# n2k-breakout-7_0-ISO.net
KiCad netlist of a schematic drawn in EAGLE
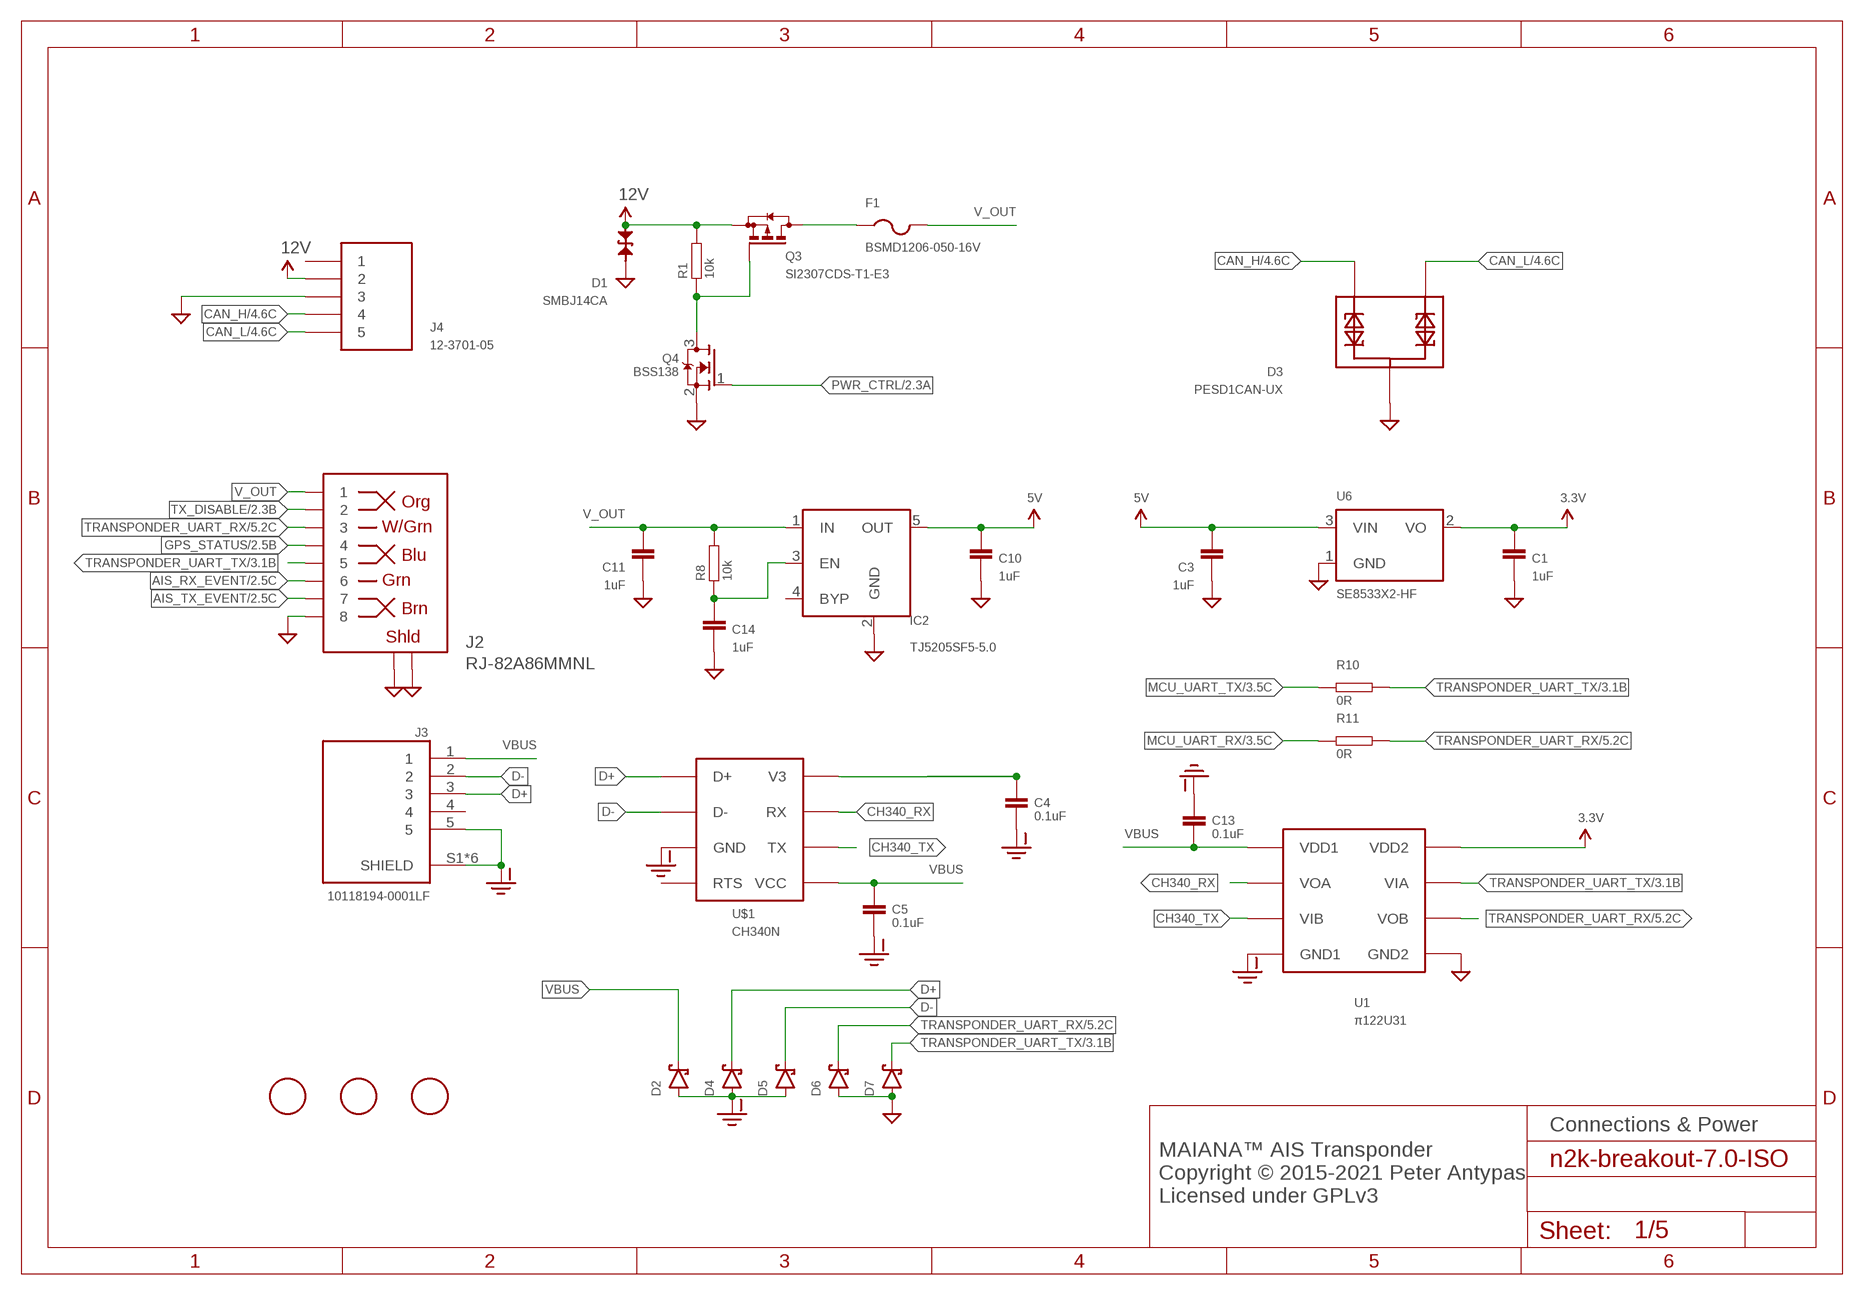
[diagram p0: schematic, sheet 1]
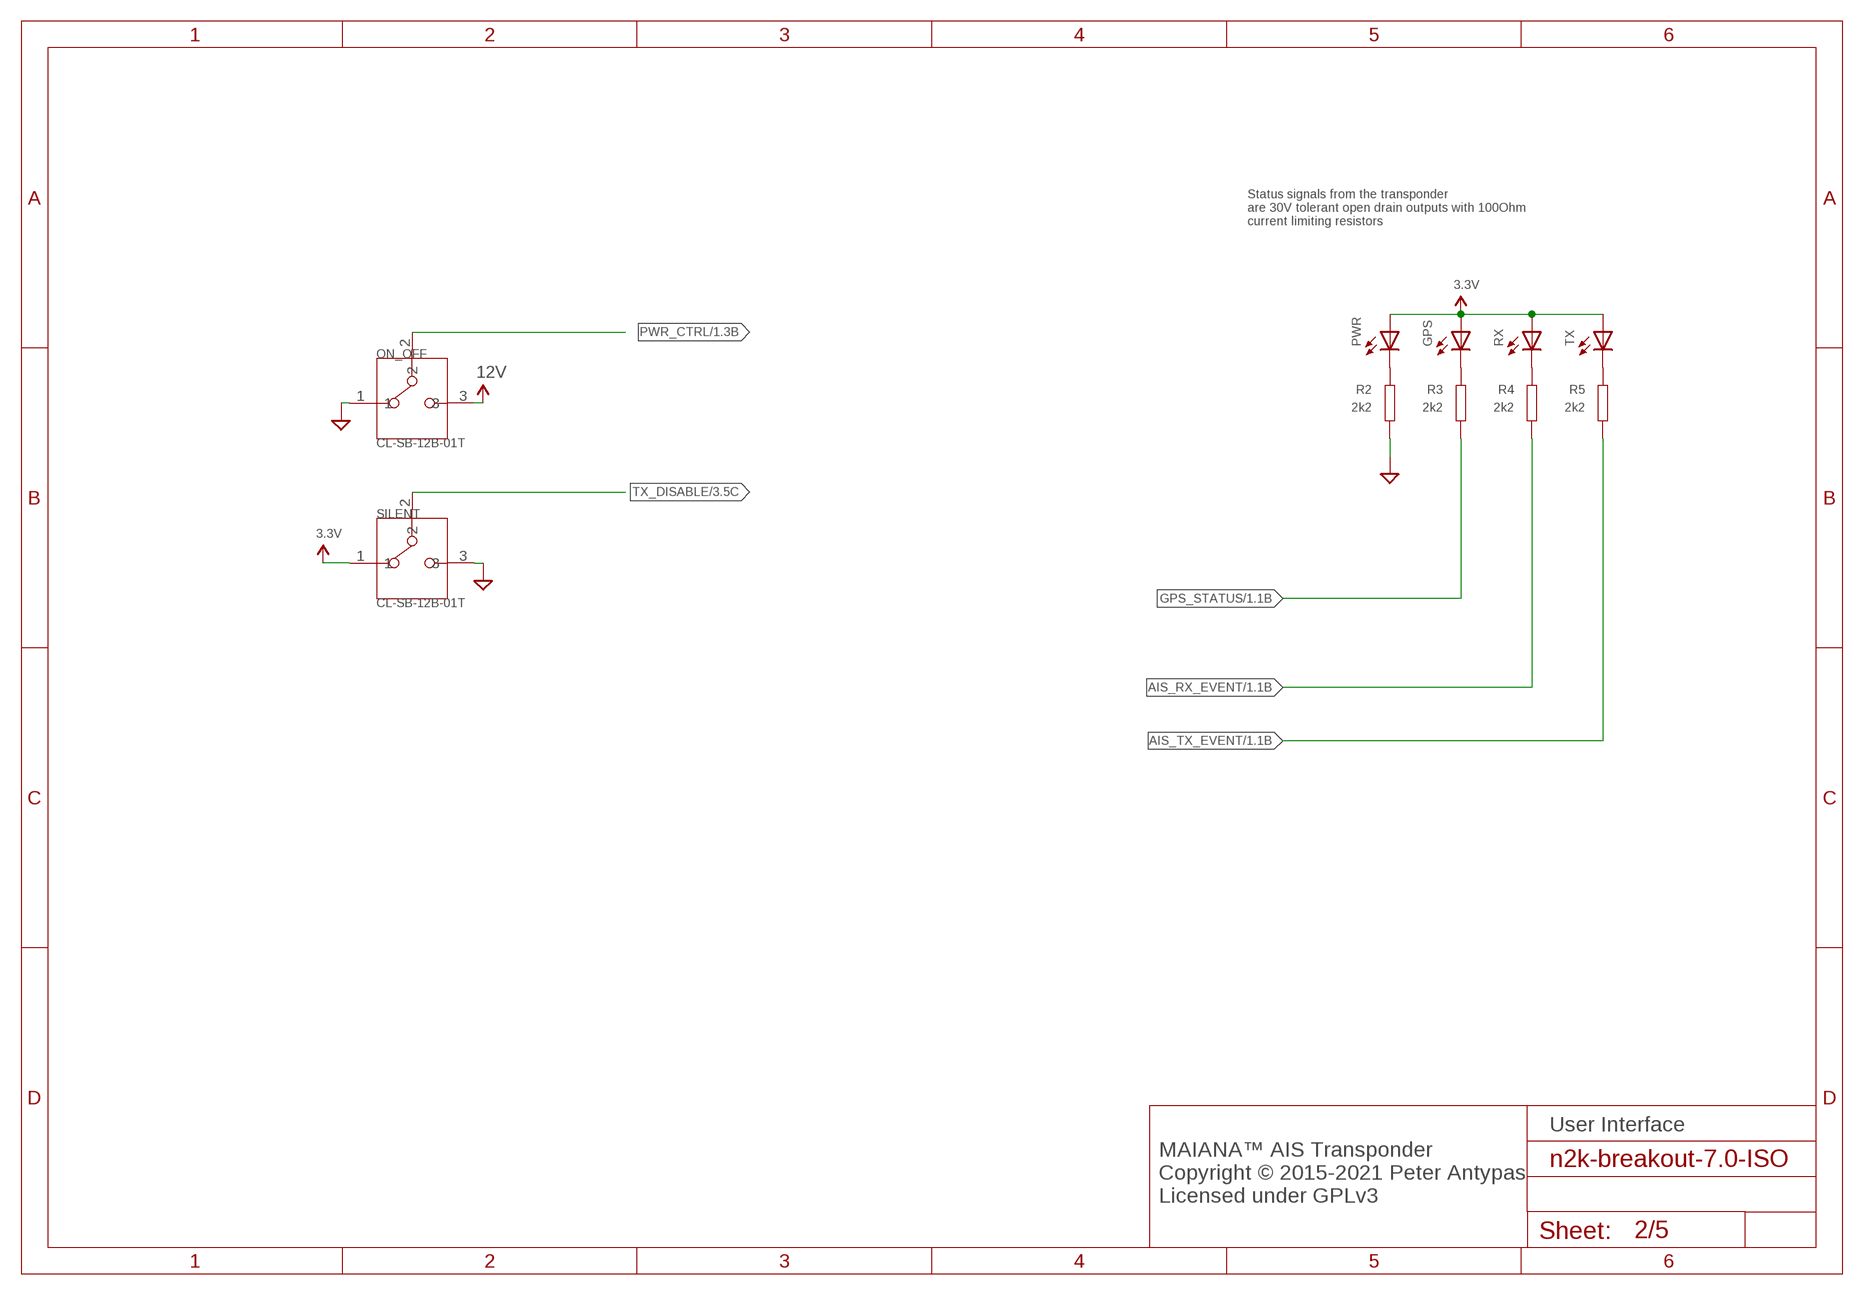
[diagram p1: schematic, sheet 2]
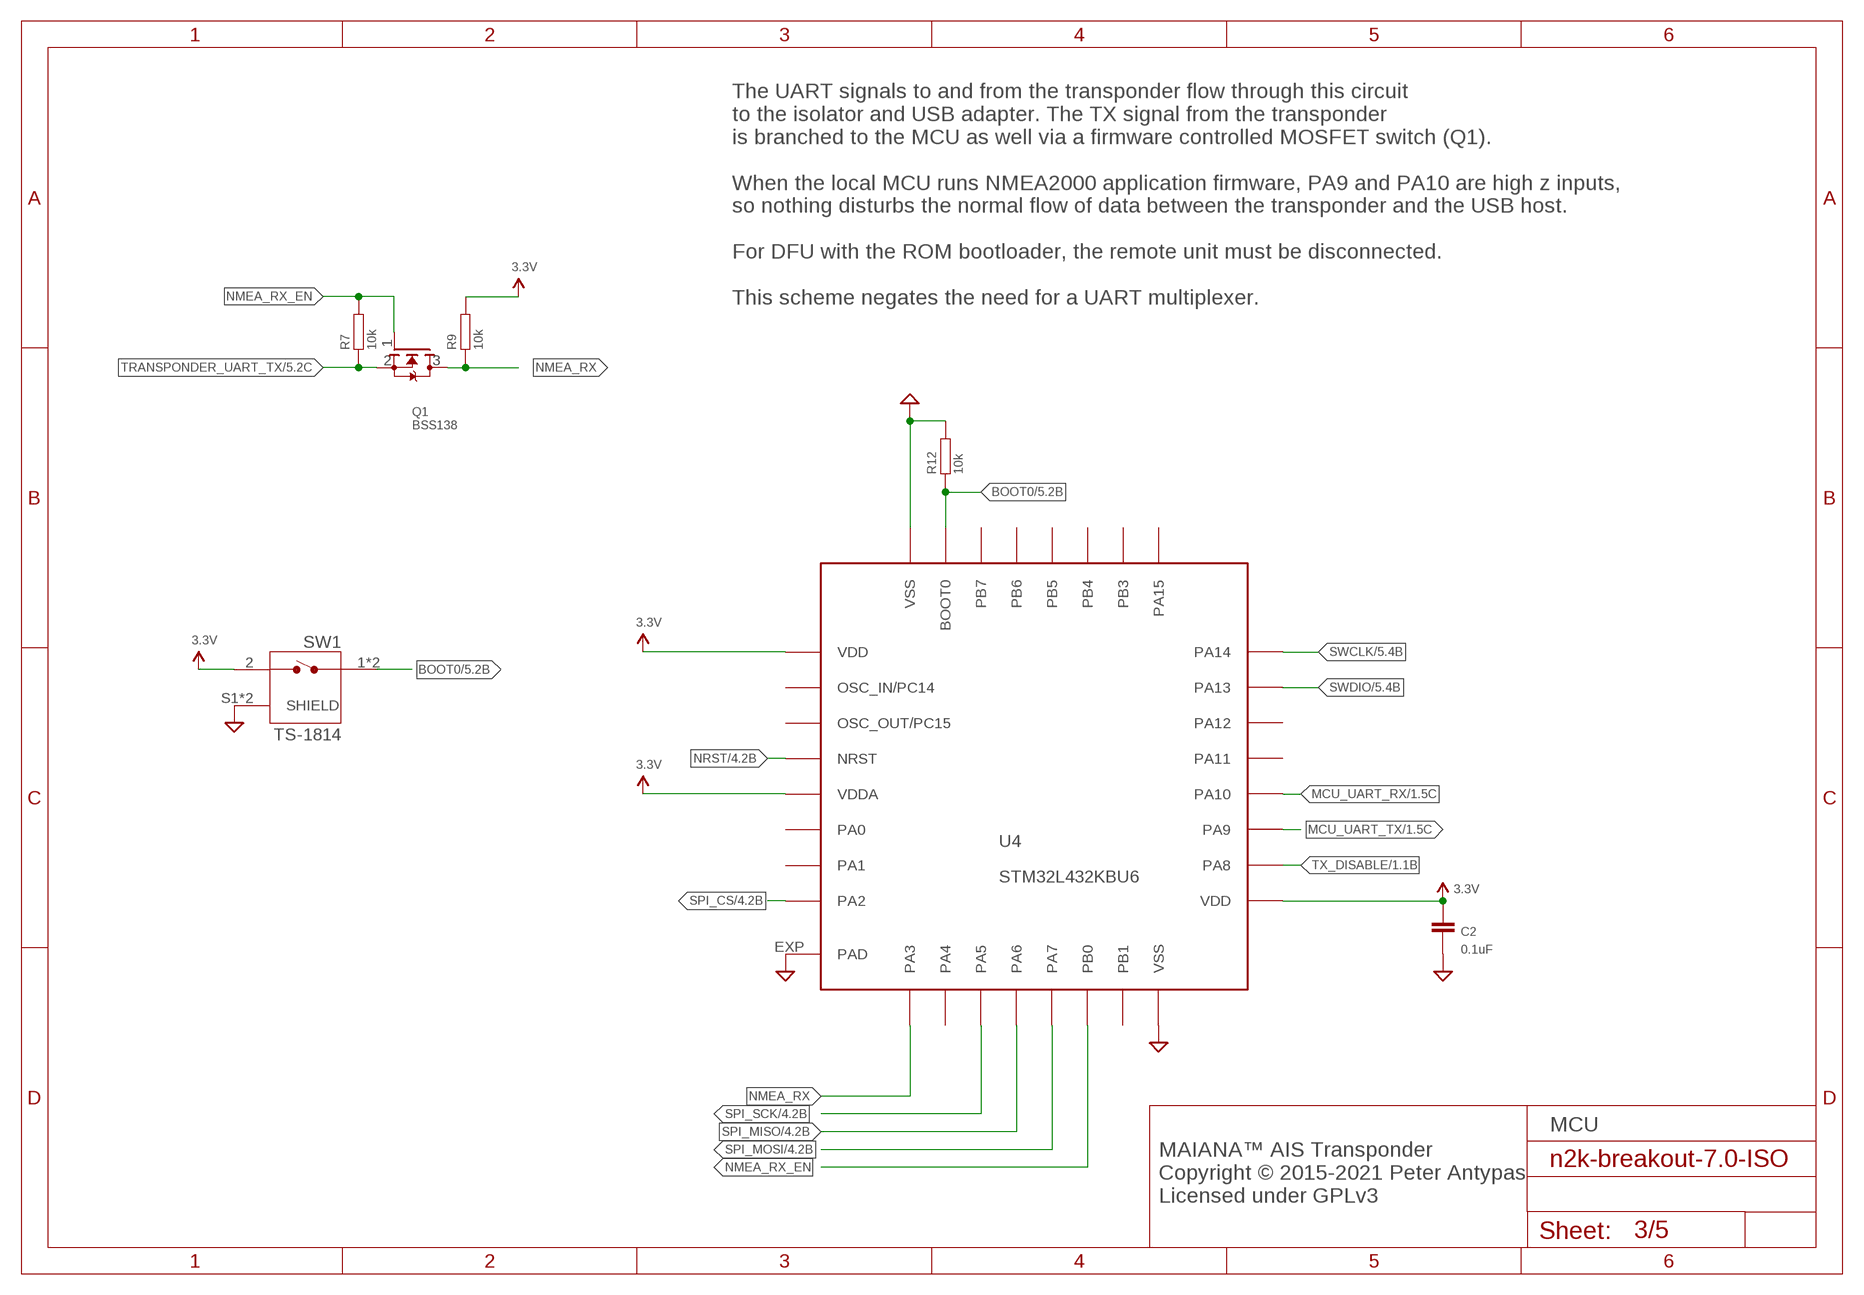
[diagram p2: schematic, sheet 3]
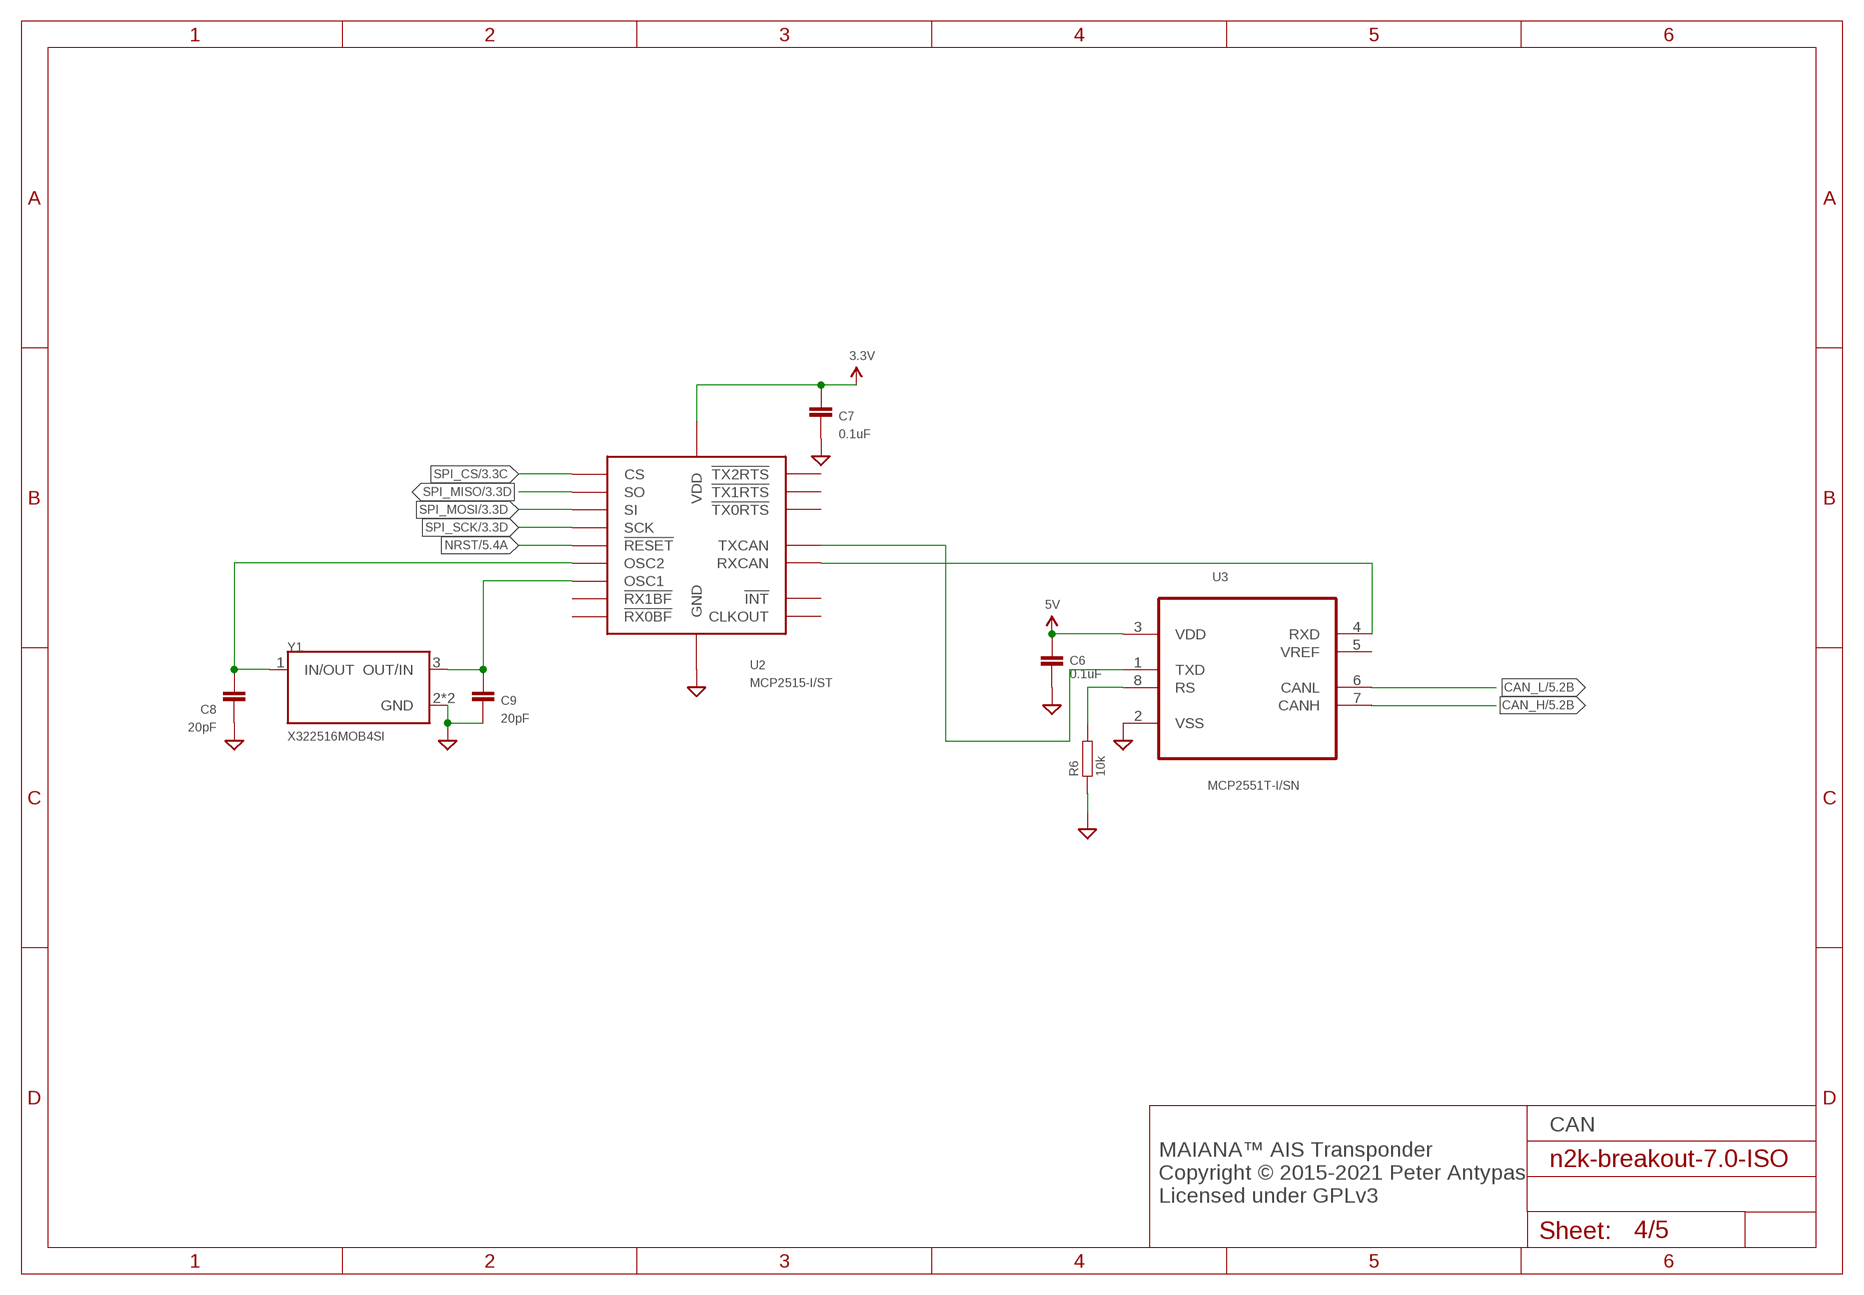
[diagram p3: schematic, sheet 4]
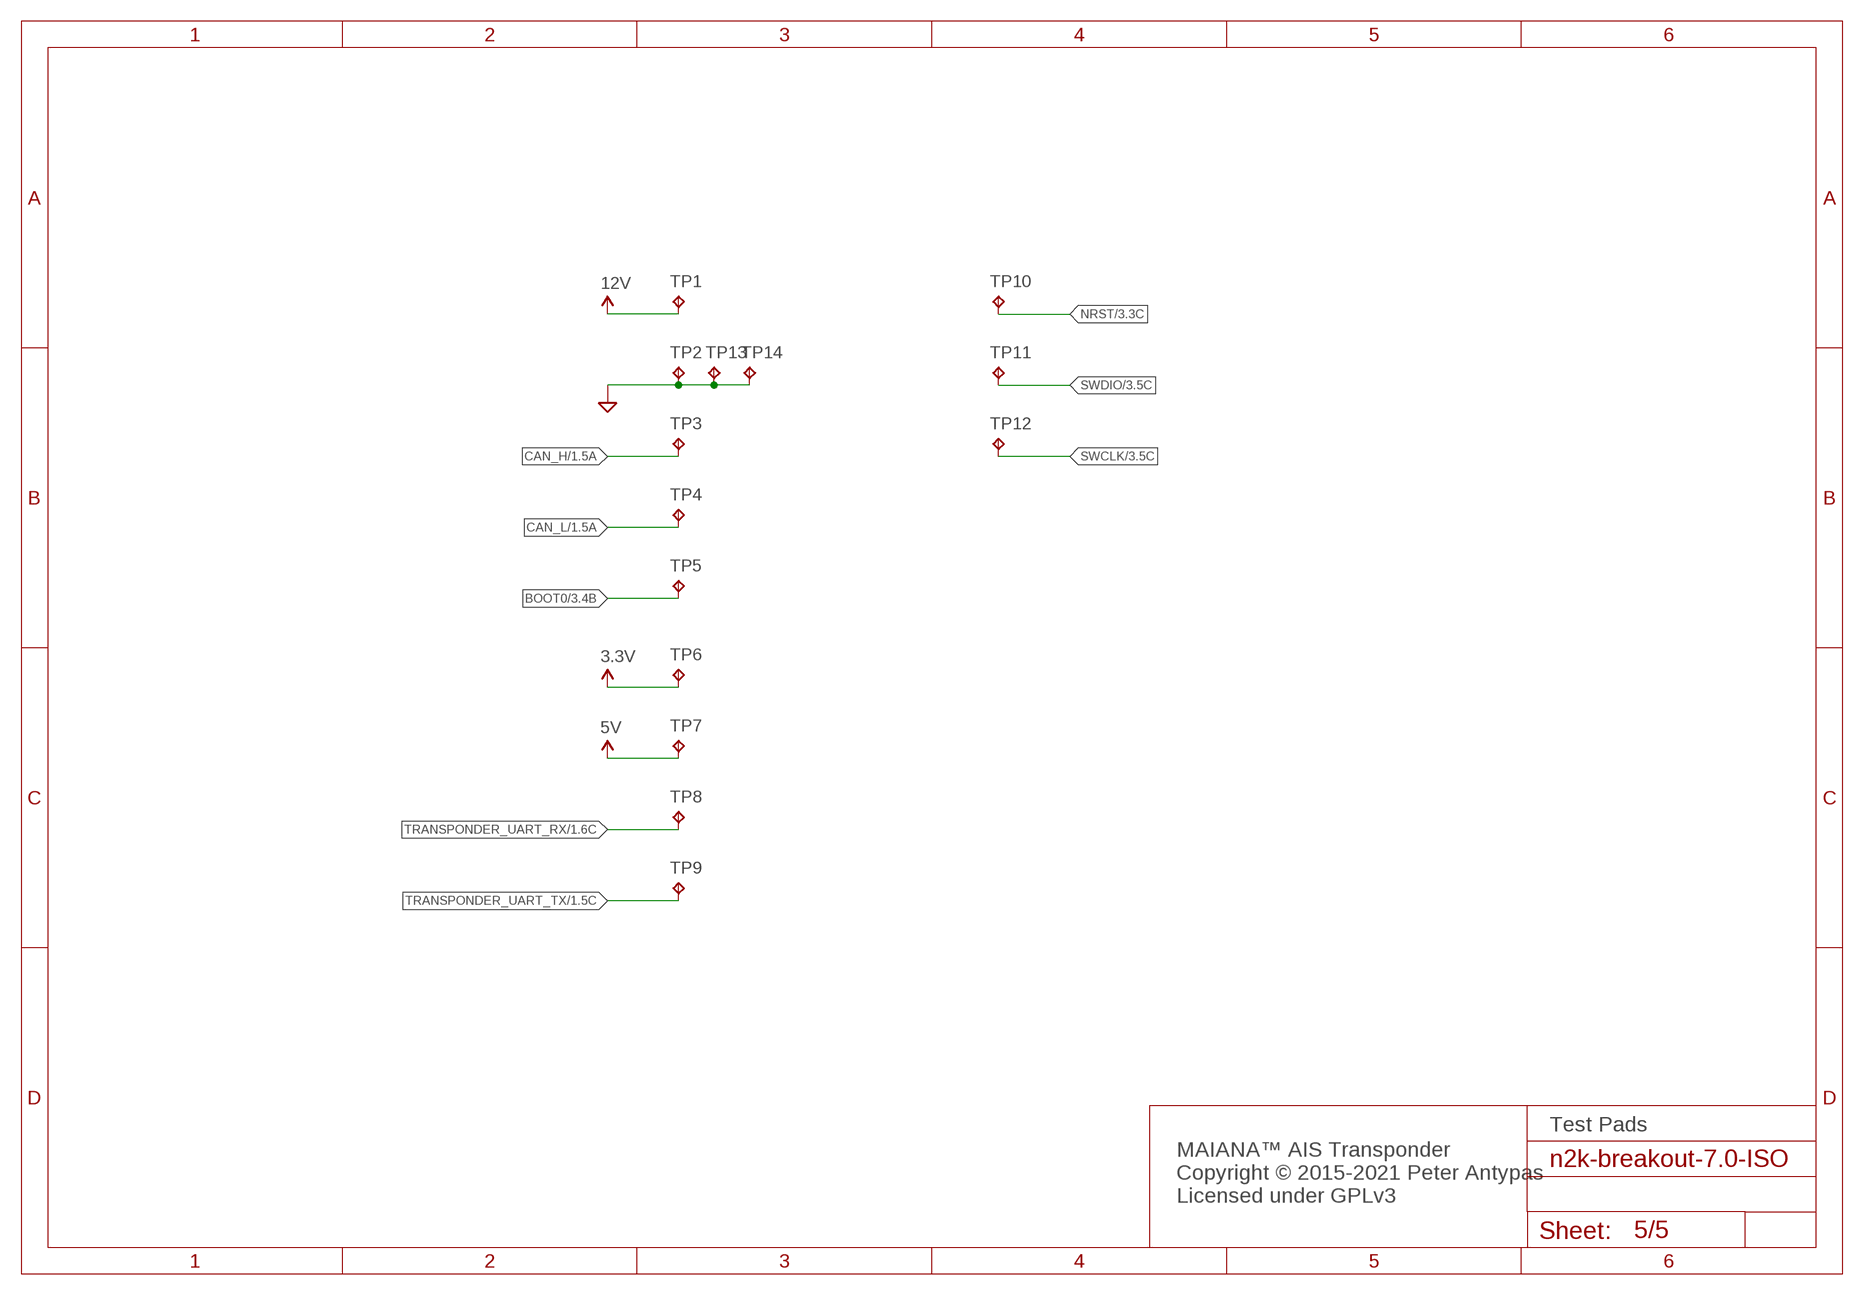
[diagram p4: schematic, sheet 5]

(export (version "E")
  (design (tool "Eeschema 10.0.6"))
  (components
    (comp (ref "TP1")
      (value "TPTP12R")
      (footprint "eagle-import:TP12R")
      (libsource (lib "eagle-import") (part "TPTP12R"))
    )
    (comp (ref "TP2")
      (value "TPTP12R")
      (footprint "eagle-import:TP12R")
      (libsource (lib "eagle-import") (part "TPTP12R"))
    )
    (comp (ref "TP3")
      (value "TPTP12R")
      (footprint "eagle-import:TP12R")
      (libsource (lib "eagle-import") (part "TPTP12R"))
    )
    (comp (ref "TP4")
      (value "TPTP12R")
      (footprint "eagle-import:TP12R")
      (libsource (lib "eagle-import") (part "TPTP12R"))
    )
    (comp (ref "TP5")
      (value "TPTP12R")
      (footprint "eagle-import:TP12R")
      (libsource (lib "eagle-import") (part "TPTP12R"))
    )
    (comp (ref "TP6")
      (value "TPTP12R")
      (footprint "eagle-import:TP12R")
      (libsource (lib "eagle-import") (part "TPTP12R"))
    )
    (comp (ref "TP7")
      (value "TPTP12R")
      (footprint "eagle-import:TP12R")
      (libsource (lib "eagle-import") (part "TPTP12R"))
    )
    (comp (ref "TP8")
      (value "TPTP12R")
      (footprint "eagle-import:TP12R")
      (libsource (lib "eagle-import") (part "TPTP12R"))
    )
    (comp (ref "TP9")
      (value "TPTP12R")
      (footprint "eagle-import:TP12R")
      (libsource (lib "eagle-import") (part "TPTP12R"))
    )
    (comp (ref "TP10")
      (value "TPTP12R")
      (footprint "eagle-import:TP12R")
      (libsource (lib "eagle-import") (part "TPTP12R"))
    )
    (comp (ref "TP11")
      (value "TPTP12R")
      (footprint "eagle-import:TP12R")
      (libsource (lib "eagle-import") (part "TPTP12R"))
    )
    (comp (ref "TP12")
      (value "TPTP12R")
      (footprint "eagle-import:TP12R")
      (libsource (lib "eagle-import") (part "TPTP12R"))
    )
    (comp (ref "TP13")
      (value "TPTP12R")
      (footprint "eagle-import:TP12R")
      (libsource (lib "eagle-import") (part "TPTP12R"))
    )
    (comp (ref "TP14")
      (value "TPTP12R")
      (footprint "eagle-import:TP12R")
      (libsource (lib "eagle-import") (part "TPTP12R"))
    )
    (comp (ref "C6")
      (value "0.1uF")
      (footprint "eagle-import:0603")
      (fields (field (name "PARTNO") "06035C104KAT2A "))
      (libsource (lib "eagle-import") (part "CAPACITOR0603"))
    )
    (comp (ref "C7")
      (value "0.1uF")
      (footprint "eagle-import:0603")
      (fields (field (name "PARTNO") "06035C104KAT2A "))
      (libsource (lib "eagle-import") (part "CAPACITOR0603"))
    )
    (comp (ref "C8")
      (value "20pF")
      (footprint "eagle-import:0603")
      (fields (field (name "PARTNO") "GRM1885C1H200JA01D "))
      (libsource (lib "eagle-import") (part "CAPACITOR0603"))
    )
    (comp (ref "C9")
      (value "20pF")
      (footprint "eagle-import:0603")
      (fields (field (name "PARTNO") "GRM1885C1H200JA01D "))
      (libsource (lib "eagle-import") (part "CAPACITOR0603"))
    )
    (comp (ref "R6")
      (value "10k")
      (footprint "eagle-import:0603")
      (fields (field (name "PARTNO") "RC0603FR-0710KL"))
      (libsource (lib "eagle-import") (part "RESISTOR0603"))
    )
    (comp (ref "U2")
      (value "MCP2515-I/ST")
      (footprint "eagle-import:TSSOP20")
      (libsource (lib "eagle-import") (part "MCP2515TSSOP20"))
    )
    (comp (ref "U3")
      (value "MCP2551T-I/SN")
      (footprint "eagle-import:SOIC127P600X175-8N")
      (fields (field (name "MF") "Microchip"))
      (libsource (lib "eagle-import") (part "MCP2551T-I/SN"))
    )
    (comp (ref "Y1")
      (value "X322516MOB4SI")
      (footprint "eagle-import:XTAL_ECS-160-10-36-JGN-TR")
      (fields (field (name "MF") "ECS Inc.") (field (name "MP") "ECS-300-8-36CKM-TR"))
      (libsource (lib "eagle-import") (part "ECS-300-8-36CKM-TR"))
    )
    (comp (ref "C1")
      (value "1uF")
      (footprint "eagle-import:0603")
      (fields (field (name "PARTNO") "CC0603KRX5R8BB105"))
      (libsource (lib "eagle-import") (part "CAPACITOR0603"))
    )
    (comp (ref "C3")
      (value "1uF")
      (footprint "eagle-import:0603")
      (fields (field (name "PARTNO") "CC0603KRX5R8BB105"))
      (libsource (lib "eagle-import") (part "CAPACITOR0603"))
    )
    (comp (ref "C4")
      (value "0.1uF")
      (footprint "eagle-import:0603")
      (fields (field (name "PARTNO") "06035C104KAT2A "))
      (libsource (lib "eagle-import") (part "CAPACITOR0603"))
    )
    (comp (ref "C5")
      (value "0.1uF")
      (footprint "eagle-import:0603")
      (fields (field (name "PARTNO") "06035C104KAT2A "))
      (libsource (lib "eagle-import") (part "CAPACITOR0603"))
    )
    (comp (ref "C10")
      (value "1uF")
      (footprint "eagle-import:0603")
      (fields (field (name "PARTNO") "CC0603KRX5R8BB105"))
      (libsource (lib "eagle-import") (part "CAPACITOR0603"))
    )
    (comp (ref "C11")
      (value "1uF")
      (footprint "eagle-import:0603")
      (fields (field (name "PARTNO") "CC0603KRX5R8BB105"))
      (libsource (lib "eagle-import") (part "CAPACITOR0603"))
    )
    (comp (ref "C13")
      (value "0.1uF")
      (footprint "eagle-import:0603")
      (fields (field (name "PARTNO") "06035C104KAT2A "))
      (libsource (lib "eagle-import") (part "CAPACITOR0603"))
    )
    (comp (ref "C14")
      (value "1uF")
      (footprint "eagle-import:0603")
      (fields (field (name "PARTNO") "CC0603KRX5R8BB105"))
      (libsource (lib "eagle-import") (part "CAPACITOR0603"))
    )
    (comp (ref "D1")
      (value "SMBJ14CA")
      (footprint "eagle-import:SMB-BIDIR")
      (fields (field (name "PARTNO") "SMBJ14CA "))
      (libsource (lib "eagle-import") (part "DIODE-TVS-BIDIRSMB"))
    )
    (comp (ref "D2")
      (value "DIODE-SCHOTTKYSOD323")
      (footprint "eagle-import:SOD323")
      (libsource (lib "eagle-import") (part "DIODE-SCHOTTKYSOD323"))
    )
    (comp (ref "D3")
      (value "PESD1CAN-UX")
      (footprint "eagle-import:SOT65P210X110-3N")
      (libsource (lib "eagle-import") (part "PESD1CAN-UX"))
    )
    (comp (ref "D4")
      (value "DIODE-SCHOTTKYSOD323")
      (footprint "eagle-import:SOD323")
      (libsource (lib "eagle-import") (part "DIODE-SCHOTTKYSOD323"))
    )
    (comp (ref "D5")
      (value "DIODE-SCHOTTKYSOD323")
      (footprint "eagle-import:SOD323")
      (libsource (lib "eagle-import") (part "DIODE-SCHOTTKYSOD323"))
    )
    (comp (ref "D6")
      (value "DIODE-SCHOTTKYSOD323")
      (footprint "eagle-import:SOD323")
      (libsource (lib "eagle-import") (part "DIODE-SCHOTTKYSOD323"))
    )
    (comp (ref "D7")
      (value "DIODE-SCHOTTKYSOD323")
      (footprint "eagle-import:SOD323")
      (libsource (lib "eagle-import") (part "DIODE-SCHOTTKYSOD323"))
    )
    (comp (ref "F1")
      (value "BSMD1206-050-16V")
      (footprint "eagle-import:R1206")
      (fields (field (name "PARTNO") "BSMD1206-050-16V "))
      (libsource (lib "eagle-import") (part "PTCFUSE-1206"))
    )
    (comp (ref "IC2")
      (value "TJ5205SF5-5.0")
      (footprint "eagle-import:SOT23-5")
      (fields (field (name "PARTNO") "TJ5205SF5-5.0 "))
      (libsource (lib "eagle-import") (part "MIC5219XX"))
    )
    (comp (ref "J2")
      (value "RJ-82A86MMNL")
      (footprint "eagle-import:RJ-82A86MMNL")
      (libsource (lib "eagle-import") (part "RJ-82A86MMNL"))
    )
    (comp (ref "J3")
      (value "10118194-0001LF")
      (footprint "eagle-import:AMPHENOL_10118194-0001LF")
      (fields (field (name "MF") "Amphenol ICC (FCI)"))
      (libsource (lib "eagle-import") (part "10118194-0001LF"))
    )
    (comp (ref "J4")
      (value "12-3701-05")
      (footprint "eagle-import:MICRO_C_5PIN")
      (libsource (lib "eagle-import") (part "12-3701-05"))
    )
    (comp (ref "Q3")
      (value "SI2307CDS-T1-E3")
      (footprint "eagle-import:SOT23")
      (fields (field (name "PARTNO") "SI2307CDS-T1-E3 "))
      (libsource (lib "eagle-import") (part "BSS84"))
    )
    (comp (ref "Q4")
      (value "BSS138")
      (footprint "eagle-import:SOT23")
      (libsource (lib "eagle-import") (part "MOSFET-NREFLOW"))
    )
    (comp (ref "R1")
      (value "10k")
      (footprint "eagle-import:0603")
      (fields (field (name "PARTNO") "RC0603FR-0710KL"))
      (libsource (lib "eagle-import") (part "RESISTOR0603"))
    )
    (comp (ref "R8")
      (value "10k")
      (footprint "eagle-import:0603")
      (fields (field (name "PARTNO") "RC0603FR-0710KL"))
      (libsource (lib "eagle-import") (part "RESISTOR0603"))
    )
    (comp (ref "R10")
      (value "0R")
      (footprint "eagle-import:0603")
      (libsource (lib "eagle-import") (part "RESISTOR0603"))
    )
    (comp (ref "R11")
      (value "0R")
      (footprint "eagle-import:0603")
      (libsource (lib "eagle-import") (part "RESISTOR0603"))
    )
    (comp (ref "U$1")
      (value "CH340N")
      (footprint "eagle-import:SOIC-8")
      (libsource (lib "eagle-import") (part "CH330N"))
    )
    (comp (ref "U$2")
      (value "FIDUCIAL")
      (footprint "eagle-import:FIDUCIAL_1MM")
      (libsource (lib "eagle-import") (part "FIDUCIAL"))
    )
    (comp (ref "U$3")
      (value "FIDUCIAL")
      (footprint "eagle-import:FIDUCIAL_1MM")
      (libsource (lib "eagle-import") (part "FIDUCIAL"))
    )
    (comp (ref "U$4")
      (value "FIDUCIAL")
      (footprint "eagle-import:FIDUCIAL_1MM")
      (libsource (lib "eagle-import") (part "FIDUCIAL"))
    )
    (comp (ref "U1")
      (value "π122U31")
      (footprint "eagle-import:SOIC8")
      (libsource (lib "eagle-import") (part "PI122U3X"))
    )
    (comp (ref "U6")
      (value "SE8533X2-HF")
      (footprint "eagle-import:SOT23")
      (libsource (lib "eagle-import") (part "MCP1799T"))
    )
    (comp (ref "C2")
      (value "0.1uF")
      (footprint "eagle-import:0603")
      (fields (field (name "PARTNO") "06035C104KAT2A "))
      (libsource (lib "eagle-import") (part "CAPACITOR0603"))
    )
    (comp (ref "Q1")
      (value "BSS138")
      (footprint "eagle-import:SOT23")
      (libsource (lib "eagle-import") (part "MOSFET-NREFLOW"))
    )
    (comp (ref "R7")
      (value "10k")
      (footprint "eagle-import:0603")
      (fields (field (name "PARTNO") "RC0603FR-0710KL"))
      (libsource (lib "eagle-import") (part "RESISTOR0603"))
    )
    (comp (ref "R9")
      (value "10k")
      (footprint "eagle-import:0603")
      (fields (field (name "PARTNO") "RC0603FR-0710KL"))
      (libsource (lib "eagle-import") (part "RESISTOR0603"))
    )
    (comp (ref "R12")
      (value "10k")
      (footprint "eagle-import:0603")
      (fields (field (name "PARTNO") "RC0603FR-0710KL"))
      (libsource (lib "eagle-import") (part "RESISTOR0603"))
    )
    (comp (ref "SW1")
      (value "TS-1814")
      (footprint "eagle-import:TE_1977066-1")
      (fields (field (name "COMMENT") "1977066-1") (field (name "MF") "TE Connectivity"))
      (libsource (lib "eagle-import") (part "1977066-1"))
    )
    (comp (ref "U4")
      (value "STM32L432KBU6")
      (footprint "eagle-import:QFN32")
      (fields (field (name "PARTNO") "STM32L422KBU6"))
      (libsource (lib "eagle-import") (part "STM32L432KXXX"))
    )
    (comp (ref "GPS")
      (value "LEDCHIPLED_1206")
      (footprint "eagle-import:CHIPLED_1206")
      (fields (field (name "PARTNO") "TJ-S3216CL9T5ALC2G-A5"))
      (libsource (lib "eagle-import") (part "LEDCHIPLED_1206"))
    )
    (comp (ref "ON_OFF")
      (value "CL-SB-12B-01T")
      (footprint "eagle-import:CL-SB-12B")
      (fields (field (name "MF") "Nidec Copal"))
      (libsource (lib "eagle-import") (part "CL-SB-12B-01T"))
    )
    (comp (ref "PWR")
      (value "LEDCHIPLED_1206")
      (footprint "eagle-import:CHIPLED_1206")
      (fields (field (name "PARTNO") "TJ-S3216CL9T5ALC2G-A5"))
      (libsource (lib "eagle-import") (part "LEDCHIPLED_1206"))
    )
    (comp (ref "R2")
      (value "2k2")
      (footprint "eagle-import:0603")
      (fields (field (name "PARTNO") "CR0603-FX-2201ELF "))
      (libsource (lib "eagle-import") (part "RESISTOR0603"))
    )
    (comp (ref "R3")
      (value "2k2")
      (footprint "eagle-import:0603")
      (fields (field (name "PARTNO") "CR0603-FX-2201ELF"))
      (libsource (lib "eagle-import") (part "RESISTOR0603"))
    )
    (comp (ref "R4")
      (value "2k2")
      (footprint "eagle-import:0603")
      (fields (field (name "PARTNO") "CR0603-FX-2201ELF "))
      (libsource (lib "eagle-import") (part "RESISTOR0603"))
    )
    (comp (ref "R5")
      (value "2k2")
      (footprint "eagle-import:0603")
      (fields (field (name "PARTNO") "CR0603-FX-2201ELF "))
      (libsource (lib "eagle-import") (part "RESISTOR0603"))
    )
    (comp (ref "RX")
      (value "LEDCHIPLED_1206")
      (footprint "eagle-import:CHIPLED_1206")
      (fields (field (name "PARTNO") "TJ-S3216CL9T5ALC2G-A5"))
      (libsource (lib "eagle-import") (part "LEDCHIPLED_1206"))
    )
    (comp (ref "SILENT")
      (value "CL-SB-12B-01T")
      (footprint "eagle-import:CL-SB-12B")
      (fields (field (name "MF") "Nidec Copal"))
      (libsource (lib "eagle-import") (part "CL-SB-12B-01T"))
    )
    (comp (ref "TX")
      (value "LEDCHIPLED_1206")
      (footprint "eagle-import:CHIPLED_1206")
      (fields (field (name "PARTNO") "TJ-S3216CL9T5ALC2G-A5"))
      (libsource (lib "eagle-import") (part "LEDCHIPLED_1206"))
    )
  )
  (nets
    (net (code "1") (name "3.3V") (class "Default")
      (node (ref "C1") (pin "P$1") (pinfunction "1_P$1") (pintype "passive"))
      (node (ref "C2") (pin "P$1") (pinfunction "1_P$1") (pintype "passive"))
      (node (ref "C7") (pin "P$1") (pinfunction "1_P$1") (pintype "passive"))
      (node (ref "GPS") (pin "A") (pinfunction "A_A") (pintype "passive"))
      (node (ref "PWR") (pin "A") (pinfunction "A_A") (pintype "passive"))
      (node (ref "R9") (pin "P$2") (pinfunction "P$2_P$2") (pintype "passive"))
      (node (ref "RX") (pin "A") (pinfunction "A_A") (pintype "passive"))
      (node (ref "SILENT") (pin "1") (pinfunction "1_1") (pintype "bidirectional"))
      (node (ref "SW1") (pin "2") (pinfunction "2_2") (pintype "passive"))
      (node (ref "TP6") (pin "TP") (pinfunction "TP_TP") (pintype "input"))
      (node (ref "TX") (pin "A") (pinfunction "A_A") (pintype "passive"))
      (node (ref "U1") (pin "8") (pinfunction "VDD2_8") (pintype "bidirectional"))
      (node (ref "U2") (pin "20") (pinfunction "VDD_20") (pintype "bidirectional"))
      (node (ref "U4") (pin "1") (pinfunction "VDD_1") (pintype "bidirectional"))
      (node (ref "U4") (pin "17") (pinfunction "VDD_17") (pintype "bidirectional"))
      (node (ref "U4") (pin "5") (pinfunction "VDDA_5") (pintype "bidirectional"))
      (node (ref "U6") (pin "2") (pinfunction "VO_2") (pintype "output"))
    )
    (net (code "2") (name "5V") (class "Default")
      (node (ref "C10") (pin "P$1") (pinfunction "1_P$1") (pintype "passive"))
      (node (ref "C3") (pin "P$1") (pinfunction "1_P$1") (pintype "passive"))
      (node (ref "C6") (pin "P$1") (pinfunction "1_P$1") (pintype "passive"))
      (node (ref "IC2") (pin "5") (pinfunction "OUT_5") (pintype "output"))
      (node (ref "TP7") (pin "TP") (pinfunction "TP_TP") (pintype "input"))
      (node (ref "U3") (pin "3") (pinfunction "VDD_3") (pintype "power_in"))
      (node (ref "U6") (pin "3") (pinfunction "VIN_3") (pintype "input"))
    )
    (net (code "3") (name "12V") (class "Default")
      (node (ref "D1") (pin "A") (pinfunction "P$1_A") (pintype "bidirectional"))
      (node (ref "J4") (pin "2") (pinfunction "2_2") (pintype "bidirectional"))
      (node (ref "ON_OFF") (pin "3") (pinfunction "3_3") (pintype "bidirectional"))
      (node (ref "Q3") (pin "2") (pinfunction "S_2") (pintype "passive"))
      (node (ref "R1") (pin "P$2") (pinfunction "P$2_P$2") (pintype "passive"))
      (node (ref "TP1") (pin "TP") (pinfunction "TP_TP") (pintype "input"))
    )
    (net (code "4") (name "AIS_RX_EVENT") (class "Default")
      (node (ref "J2") (pin "P$6") (pinfunction "6_P$6") (pintype "bidirectional"))
      (node (ref "R4") (pin "P$2") (pinfunction "P$2_P$2") (pintype "passive"))
    )
    (net (code "5") (name "AIS_TX_EVENT") (class "Default")
      (node (ref "J2") (pin "P$7") (pinfunction "7_P$7") (pintype "bidirectional"))
      (node (ref "R5") (pin "P$2") (pinfunction "P$2_P$2") (pintype "passive"))
    )
    (net (code "6") (name "BOOT0") (class "Default")
      (node (ref "R12") (pin "P$1") (pinfunction "P$1_P$1") (pintype "passive"))
      (node (ref "SW1") (pin "1") (pinfunction "1_1") (pintype "passive"))
      (node (ref "SW1") (pin "3") (pinfunction "1_3") (pintype "passive"))
      (node (ref "TP5") (pin "TP") (pinfunction "TP_TP") (pintype "input"))
      (node (ref "U4") (pin "31") (pinfunction "BOOT0_31") (pintype "bidirectional"))
    )
    (net (code "7") (name "CAN_H") (class "Default")
      (node (ref "D3") (pin "2") (pinfunction "P$2_2") (pintype "bidirectional"))
      (node (ref "J4") (pin "4") (pinfunction "4_4") (pintype "bidirectional"))
      (node (ref "TP3") (pin "TP") (pinfunction "TP_TP") (pintype "input"))
      (node (ref "U3") (pin "7") (pinfunction "CANH_7") (pintype "bidirectional"))
    )
    (net (code "8") (name "CAN_L") (class "Default")
      (node (ref "D3") (pin "1") (pinfunction "P$1_1") (pintype "bidirectional"))
      (node (ref "J4") (pin "5") (pinfunction "5_5") (pintype "bidirectional"))
      (node (ref "TP4") (pin "TP") (pinfunction "TP_TP") (pintype "input"))
      (node (ref "U3") (pin "6") (pinfunction "CANL_6") (pintype "bidirectional"))
    )
    (net (code "9") (name "CH340_RX") (class "Default")
      (node (ref "U$1") (pin "7") (pinfunction "RX_7") (pintype "bidirectional"))
      (node (ref "U1") (pin "2") (pinfunction "VOA_2") (pintype "bidirectional"))
    )
    (net (code "10") (name "CH340_TX") (class "Default")
      (node (ref "U$1") (pin "6") (pinfunction "TX_6") (pintype "bidirectional"))
      (node (ref "U1") (pin "3") (pinfunction "VIB_3") (pintype "bidirectional"))
    )
    (net (code "11") (name "D+") (class "Default")
      (node (ref "D4") (pin "C") (pinfunction "C_C") (pintype "passive"))
      (node (ref "J3") (pin "3") (pinfunction "3_3") (pintype "passive"))
      (node (ref "U$1") (pin "1") (pinfunction "D+_1") (pintype "bidirectional"))
    )
    (net (code "12") (name "D-") (class "Default")
      (node (ref "D5") (pin "C") (pinfunction "C_C") (pintype "passive"))
      (node (ref "J3") (pin "2") (pinfunction "2_2") (pintype "passive"))
      (node (ref "U$1") (pin "2") (pinfunction "D-_2") (pintype "bidirectional"))
    )
    (net (code "13") (name "GND") (class "Default")
      (node (ref "C1") (pin "P$2") (pinfunction "2_P$2") (pintype "passive"))
      (node (ref "C10") (pin "P$2") (pinfunction "2_P$2") (pintype "passive"))
      (node (ref "C11") (pin "P$2") (pinfunction "2_P$2") (pintype "passive"))
      (node (ref "C14") (pin "P$2") (pinfunction "2_P$2") (pintype "passive"))
      (node (ref "C2") (pin "P$2") (pinfunction "2_P$2") (pintype "passive"))
      (node (ref "C3") (pin "P$2") (pinfunction "2_P$2") (pintype "passive"))
      (node (ref "C6") (pin "P$2") (pinfunction "2_P$2") (pintype "passive"))
      (node (ref "C7") (pin "P$2") (pinfunction "2_P$2") (pintype "passive"))
      (node (ref "C8") (pin "P$2") (pinfunction "2_P$2") (pintype "passive"))
      (node (ref "C9") (pin "P$2") (pinfunction "2_P$2") (pintype "passive"))
      (node (ref "D1") (pin "C") (pinfunction "P$2_C") (pintype "bidirectional"))
      (node (ref "D3") (pin "3") (pinfunction "P$3_3") (pintype "bidirectional"))
      (node (ref "D6") (pin "A") (pinfunction "A_A") (pintype "passive"))
      (node (ref "D7") (pin "A") (pinfunction "A_A") (pintype "passive"))
      (node (ref "IC2") (pin "2") (pinfunction "GND_2") (pintype "power_in"))
      (node (ref "J2") (pin "P$10") (pinfunction "SHLD_P$10") (pintype "bidirectional"))
      (node (ref "J2") (pin "P$11") (pinfunction "SHLD_P$11") (pintype "bidirectional"))
      (node (ref "J2") (pin "P$12") (pinfunction "SHLD_P$12") (pintype "bidirectional"))
      (node (ref "J2") (pin "P$8") (pinfunction "8_P$8") (pintype "bidirectional"))
      (node (ref "J2") (pin "P$9") (pinfunction "SHLD_P$9") (pintype "bidirectional"))
      (node (ref "J4") (pin "3") (pinfunction "3_3") (pintype "bidirectional"))
      (node (ref "ON_OFF") (pin "1") (pinfunction "1_1") (pintype "bidirectional"))
      (node (ref "Q4") (pin "2") (pinfunction "S_2") (pintype "bidirectional"))
      (node (ref "R12") (pin "P$2") (pinfunction "P$2_P$2") (pintype "passive"))
      (node (ref "R2") (pin "P$2") (pinfunction "P$2_P$2") (pintype "passive"))
      (node (ref "R6") (pin "P$1") (pinfunction "P$1_P$1") (pintype "passive"))
      (node (ref "SILENT") (pin "3") (pinfunction "3_3") (pintype "bidirectional"))
      (node (ref "SW1") (pin "S1") (pinfunction "SHIELD_S1") (pintype "passive"))
      (node (ref "SW1") (pin "S2") (pinfunction "SHIELD_S2") (pintype "passive"))
      (node (ref "TP13") (pin "TP") (pinfunction "TP_TP") (pintype "input"))
      (node (ref "TP14") (pin "TP") (pinfunction "TP_TP") (pintype "input"))
      (node (ref "TP2") (pin "TP") (pinfunction "TP_TP") (pintype "input"))
      (node (ref "U1") (pin "5") (pinfunction "GND2_5") (pintype "bidirectional"))
      (node (ref "U2") (pin "10") (pinfunction "GND_10") (pintype "bidirectional"))
      (node (ref "U3") (pin "2") (pinfunction "VSS_2") (pintype "passive"))
      (node (ref "U4") (pin "16") (pinfunction "VSS_16") (pintype "bidirectional"))
      (node (ref "U4") (pin "32") (pinfunction "VSS_32") (pintype "bidirectional"))
      (node (ref "U4") (pin "EXP") (pinfunction "PAD_EXP") (pintype "bidirectional"))
      (node (ref "U6") (pin "1") (pinfunction "GND_1") (pintype "passive"))
      (node (ref "Y1") (pin "2") (pinfunction "GND_2") (pintype "power_in"))
      (node (ref "Y1") (pin "4") (pinfunction "GND_4") (pintype "power_in"))
    )
    (net (code "14") (name "GND-ISO") (class "Default")
      (node (ref "C13") (pin "P$1") (pinfunction "1_P$1") (pintype "passive"))
      (node (ref "C4") (pin "P$2") (pinfunction "2_P$2") (pintype "passive"))
      (node (ref "C5") (pin "P$2") (pinfunction "2_P$2") (pintype "passive"))
      (node (ref "D2") (pin "A") (pinfunction "A_A") (pintype "passive"))
      (node (ref "D4") (pin "A") (pinfunction "A_A") (pintype "passive"))
      (node (ref "D5") (pin "A") (pinfunction "A_A") (pintype "passive"))
      (node (ref "J3") (pin "5") (pinfunction "5_5") (pintype "passive"))
      (node (ref "J3") (pin "S1") (pinfunction "SHIELD_S1") (pintype "passive"))
      (node (ref "J3") (pin "S2") (pinfunction "SHIELD_S2") (pintype "passive"))
      (node (ref "J3") (pin "S3") (pinfunction "SHIELD_S3") (pintype "passive"))
      (node (ref "J3") (pin "S4") (pinfunction "SHIELD_S4") (pintype "passive"))
      (node (ref "J3") (pin "S5") (pinfunction "SHIELD_S5") (pintype "passive"))
      (node (ref "J3") (pin "S6") (pinfunction "SHIELD_S6") (pintype "passive"))
      (node (ref "U$1") (pin "3") (pinfunction "GND_3") (pintype "bidirectional"))
      (node (ref "U1") (pin "4") (pinfunction "GND1_4") (pintype "bidirectional"))
    )
    (net (code "15") (name "GPS_STATUS") (class "Default")
      (node (ref "J2") (pin "P$4") (pinfunction "4_P$4") (pintype "bidirectional"))
      (node (ref "R3") (pin "P$2") (pinfunction "P$2_P$2") (pintype "passive"))
    )
    (net (code "16") (name "MCU_UART_RX") (class "Default")
      (node (ref "R11") (pin "P$1") (pinfunction "P$1_P$1") (pintype "passive"))
      (node (ref "U4") (pin "20") (pinfunction "PA10_20") (pintype "bidirectional"))
    )
    (net (code "17") (name "MCU_UART_TX") (class "Default")
      (node (ref "R10") (pin "P$1") (pinfunction "P$1_P$1") (pintype "passive"))
      (node (ref "U4") (pin "19") (pinfunction "PA9_19") (pintype "bidirectional"))
    )
    (net (code "18") (name "NMEA_RX") (class "Default")
      (node (ref "Q1") (pin "3") (pinfunction "D_3") (pintype "bidirectional"))
      (node (ref "R9") (pin "P$1") (pinfunction "P$1_P$1") (pintype "passive"))
      (node (ref "U4") (pin "9") (pinfunction "PA3_9") (pintype "bidirectional"))
    )
    (net (code "19") (name "NMEA_RX_EN") (class "Default")
      (node (ref "Q1") (pin "1") (pinfunction "G_1") (pintype "bidirectional"))
      (node (ref "R7") (pin "P$2") (pinfunction "P$2_P$2") (pintype "passive"))
      (node (ref "U4") (pin "14") (pinfunction "PB0_14") (pintype "bidirectional"))
    )
    (net (code "20") (name "NRST") (class "Default")
      (node (ref "TP10") (pin "TP") (pinfunction "TP_TP") (pintype "input"))
      (node (ref "U2") (pin "19") (pinfunction "~{RESET}_19") (pintype "bidirectional"))
      (node (ref "U4") (pin "4") (pinfunction "NRST_4") (pintype "bidirectional"))
    )
    (net (code "21") (name "Net-(C4-1)") (class "Default")
      (node (ref "C4") (pin "P$1") (pinfunction "1_P$1") (pintype "passive"))
      (node (ref "U$1") (pin "8") (pinfunction "V3_8") (pintype "bidirectional"))
    )
    (net (code "22") (name "Net-(C8-1)") (class "Default")
      (node (ref "C8") (pin "P$1") (pinfunction "1_P$1") (pintype "passive"))
      (node (ref "U2") (pin "8") (pinfunction "OSC2_8") (pintype "bidirectional"))
      (node (ref "Y1") (pin "1") (pinfunction "IN/OUT_1") (pintype "bidirectional"))
    )
    (net (code "23") (name "Net-(C9-1)") (class "Default")
      (node (ref "C9") (pin "P$1") (pinfunction "1_P$1") (pintype "passive"))
      (node (ref "U2") (pin "9") (pinfunction "OSC1_9") (pintype "bidirectional"))
      (node (ref "Y1") (pin "3") (pinfunction "OUT/IN_3") (pintype "bidirectional"))
    )
    (net (code "24") (name "Net-(C14-1)") (class "Default")
      (node (ref "C14") (pin "P$1") (pinfunction "1_P$1") (pintype "passive"))
      (node (ref "IC2") (pin "3") (pinfunction "EN_3") (pintype "input"))
      (node (ref "R8") (pin "P$1") (pinfunction "P$1_P$1") (pintype "passive"))
    )
    (net (code "25") (name "Net-(GPS-PadC)") (class "Default")
      (node (ref "GPS") (pin "C") (pinfunction "C_C") (pintype "passive"))
      (node (ref "R3") (pin "P$1") (pinfunction "P$1_P$1") (pintype "passive"))
    )
    (net (code "26") (name "Net-(PWR-PadC)") (class "Default")
      (node (ref "PWR") (pin "C") (pinfunction "C_C") (pintype "passive"))
      (node (ref "R2") (pin "P$1") (pinfunction "P$1_P$1") (pintype "passive"))
    )
    (net (code "27") (name "Net-(Q3-D)") (class "Default")
      (node (ref "F1") (pin "1") (pinfunction "1_1") (pintype "passive"))
      (node (ref "Q3") (pin "3") (pinfunction "D_3") (pintype "passive"))
    )
    (net (code "28") (name "Net-(Q3-G)") (class "Default")
      (node (ref "Q3") (pin "1") (pinfunction "G_1") (pintype "passive"))
      (node (ref "Q4") (pin "3") (pinfunction "D_3") (pintype "bidirectional"))
      (node (ref "R1") (pin "P$1") (pinfunction "P$1_P$1") (pintype "passive"))
    )
    (net (code "29") (name "Net-(R4-PadP$1)") (class "Default")
      (node (ref "R4") (pin "P$1") (pinfunction "P$1_P$1") (pintype "passive"))
      (node (ref "RX") (pin "C") (pinfunction "C_C") (pintype "passive"))
    )
    (net (code "30") (name "Net-(R5-PadP$1)") (class "Default")
      (node (ref "R5") (pin "P$1") (pinfunction "P$1_P$1") (pintype "passive"))
      (node (ref "TX") (pin "C") (pinfunction "C_C") (pintype "passive"))
    )
    (net (code "31") (name "Net-(U2-RXCAN)") (class "Default")
      (node (ref "U2") (pin "2") (pinfunction "RXCAN_2") (pintype "bidirectional"))
      (node (ref "U3") (pin "4") (pinfunction "RXD_4") (pintype "output"))
    )
    (net (code "32") (name "Net-(U2-TXCAN)") (class "Default")
      (node (ref "U2") (pin "1") (pinfunction "TXCAN_1") (pintype "bidirectional"))
      (node (ref "U3") (pin "1") (pinfunction "TXD_1") (pintype "input"))
    )
    (net (code "33") (name "Net-(U3-RS)") (class "Default")
      (node (ref "R6") (pin "P$2") (pinfunction "P$2_P$2") (pintype "passive"))
      (node (ref "U3") (pin "8") (pinfunction "RS_8") (pintype "input"))
    )
    (net (code "34") (name "PWR_CTRL") (class "Default")
      (node (ref "ON_OFF") (pin "2") (pinfunction "2_2") (pintype "bidirectional"))
      (node (ref "Q4") (pin "1") (pinfunction "G_1") (pintype "bidirectional"))
    )
    (net (code "35") (name "SPI_CS") (class "Default")
      (node (ref "U2") (pin "18") (pinfunction "CS_18") (pintype "bidirectional"))
      (node (ref "U4") (pin "8") (pinfunction "PA2_8") (pintype "bidirectional"))
    )
    (net (code "36") (name "SPI_MISO") (class "Default")
      (node (ref "U2") (pin "17") (pinfunction "SO_17") (pintype "bidirectional"))
      (node (ref "U4") (pin "12") (pinfunction "PA6_12") (pintype "bidirectional"))
    )
    (net (code "37") (name "SPI_MOSI") (class "Default")
      (node (ref "U2") (pin "16") (pinfunction "SI_16") (pintype "bidirectional"))
      (node (ref "U4") (pin "13") (pinfunction "PA7_13") (pintype "bidirectional"))
    )
    (net (code "38") (name "SPI_SCK") (class "Default")
      (node (ref "U2") (pin "14") (pinfunction "SCK_14") (pintype "bidirectional"))
      (node (ref "U4") (pin "11") (pinfunction "PA5_11") (pintype "bidirectional"))
    )
    (net (code "39") (name "SWCLK") (class "Default")
      (node (ref "TP12") (pin "TP") (pinfunction "TP_TP") (pintype "input"))
      (node (ref "U4") (pin "24") (pinfunction "PA14_24") (pintype "bidirectional"))
    )
    (net (code "40") (name "SWDIO") (class "Default")
      (node (ref "TP11") (pin "TP") (pinfunction "TP_TP") (pintype "input"))
      (node (ref "U4") (pin "23") (pinfunction "PA13_23") (pintype "bidirectional"))
    )
    (net (code "41") (name "TRANSPONDER_UART_RX") (class "Default")
      (node (ref "D6") (pin "C") (pinfunction "C_C") (pintype "passive"))
      (node (ref "J2") (pin "P$3") (pinfunction "3_P$3") (pintype "bidirectional"))
      (node (ref "R11") (pin "P$2") (pinfunction "P$2_P$2") (pintype "passive"))
      (node (ref "TP8") (pin "TP") (pinfunction "TP_TP") (pintype "input"))
      (node (ref "U1") (pin "6") (pinfunction "VOB_6") (pintype "bidirectional"))
    )
    (net (code "42") (name "TRANSPONDER_UART_TX") (class "Default")
      (node (ref "D7") (pin "C") (pinfunction "C_C") (pintype "passive"))
      (node (ref "J2") (pin "P$5") (pinfunction "5_P$5") (pintype "bidirectional"))
      (node (ref "Q1") (pin "2") (pinfunction "S_2") (pintype "bidirectional"))
      (node (ref "R10") (pin "P$2") (pinfunction "P$2_P$2") (pintype "passive"))
      (node (ref "R7") (pin "P$1") (pinfunction "P$1_P$1") (pintype "passive"))
      (node (ref "TP9") (pin "TP") (pinfunction "TP_TP") (pintype "input"))
      (node (ref "U1") (pin "7") (pinfunction "VIA_7") (pintype "bidirectional"))
    )
    (net (code "43") (name "TX_DISABLE") (class "Default")
      (node (ref "J2") (pin "P$2") (pinfunction "2_P$2") (pintype "bidirectional"))
      (node (ref "SILENT") (pin "2") (pinfunction "2_2") (pintype "bidirectional"))
      (node (ref "U4") (pin "18") (pinfunction "PA8_18") (pintype "bidirectional"))
    )
    (net (code "44") (name "VBUS") (class "Default")
      (node (ref "C13") (pin "P$2") (pinfunction "2_P$2") (pintype "passive"))
      (node (ref "C5") (pin "P$1") (pinfunction "1_P$1") (pintype "passive"))
      (node (ref "D2") (pin "C") (pinfunction "C_C") (pintype "passive"))
      (node (ref "J3") (pin "1") (pinfunction "1_1") (pintype "passive"))
      (node (ref "U$1") (pin "5") (pinfunction "VCC_5") (pintype "bidirectional"))
      (node (ref "U1") (pin "1") (pinfunction "VDD1_1") (pintype "bidirectional"))
    )
    (net (code "45") (name "V_OUT") (class "Default")
      (node (ref "C11") (pin "P$1") (pinfunction "1_P$1") (pintype "passive"))
      (node (ref "F1") (pin "2") (pinfunction "2_2") (pintype "passive"))
      (node (ref "IC2") (pin "1") (pinfunction "IN_1") (pintype "input"))
      (node (ref "J2") (pin "P$1") (pinfunction "1_P$1") (pintype "bidirectional"))
      (node (ref "R8") (pin "P$2") (pinfunction "P$2_P$2") (pintype "passive"))
    )
    (net (code "46") (name "unconnected-(IC2-BYP-Pad4)") (class "Default")
      (node (ref "IC2") (pin "4") (pinfunction "BYP_4") (pintype "passive"))
    )
    (net (code "47") (name "unconnected-(J3-Pad4)") (class "Default")
      (node (ref "J3") (pin "4") (pinfunction "4_4") (pintype "passive"))
    )
    (net (code "48") (name "unconnected-(J4-Pad1)") (class "Default")
      (node (ref "J4") (pin "1") (pinfunction "1_1") (pintype "bidirectional"))
    )
    (net (code "49") (name "unconnected-(U$1-RTS-Pad4)") (class "Default")
      (node (ref "U$1") (pin "4") (pinfunction "RTS_4") (pintype "bidirectional"))
    )
    (net (code "50") (name "unconnected-(U2-CLKOUT-Pad3)") (class "Default")
      (node (ref "U2") (pin "3") (pinfunction "CLKOUT_3") (pintype "bidirectional"))
    )
    (net (code "51") (name "unconnected-(U2-~{INT}-Pad13)") (class "Default")
      (node (ref "U2") (pin "13") (pinfunction "~{INT}_13") (pintype "bidirectional"))
    )
    (net (code "52") (name "unconnected-(U2-~{RX0BF}-Pad12)") (class "Default")
      (node (ref "U2") (pin "12") (pinfunction "~{RX0BF}_12") (pintype "bidirectional"))
    )
    (net (code "53") (name "unconnected-(U2-~{RX1BF}-Pad11)") (class "Default")
      (node (ref "U2") (pin "11") (pinfunction "~{RX1BF}_11") (pintype "bidirectional"))
    )
    (net (code "54") (name "unconnected-(U2-~{TX0RTS}-Pad4)") (class "Default")
      (node (ref "U2") (pin "4") (pinfunction "~{TX0RTS}_4") (pintype "bidirectional"))
    )
    (net (code "55") (name "unconnected-(U2-~{TX1RTS}-Pad5)") (class "Default")
      (node (ref "U2") (pin "5") (pinfunction "~{TX1RTS}_5") (pintype "bidirectional"))
    )
    (net (code "56") (name "unconnected-(U2-~{TX2RTS}-Pad7)") (class "Default")
      (node (ref "U2") (pin "7") (pinfunction "~{TX2RTS}_7") (pintype "bidirectional"))
    )
    (net (code "57") (name "unconnected-(U3-VREF-Pad5)") (class "Default")
      (node (ref "U3") (pin "5") (pinfunction "VREF_5") (pintype "output"))
    )
    (net (code "58") (name "unconnected-(U4-OSC_IN{slash}PC14-Pad2)") (class "Default")
      (node (ref "U4") (pin "2") (pinfunction "OSC_IN/PC14_2") (pintype "bidirectional"))
    )
    (net (code "59") (name "unconnected-(U4-OSC_OUT{slash}PC15-Pad3)") (class "Default")
      (node (ref "U4") (pin "3") (pinfunction "OSC_OUT/PC15_3") (pintype "bidirectional"))
    )
    (net (code "60") (name "unconnected-(U4-PA0-Pad6)") (class "Default")
      (node (ref "U4") (pin "6") (pinfunction "PA0_6") (pintype "bidirectional"))
    )
    (net (code "61") (name "unconnected-(U4-PA1-Pad7)") (class "Default")
      (node (ref "U4") (pin "7") (pinfunction "PA1_7") (pintype "bidirectional"))
    )
    (net (code "62") (name "unconnected-(U4-PA4-Pad10)") (class "Default")
      (node (ref "U4") (pin "10") (pinfunction "PA4_10") (pintype "bidirectional"))
    )
    (net (code "63") (name "unconnected-(U4-PA11-Pad21)") (class "Default")
      (node (ref "U4") (pin "21") (pinfunction "PA11_21") (pintype "bidirectional"))
    )
    (net (code "64") (name "unconnected-(U4-PA12-Pad22)") (class "Default")
      (node (ref "U4") (pin "22") (pinfunction "PA12_22") (pintype "bidirectional"))
    )
    (net (code "65") (name "unconnected-(U4-PA15-Pad25)") (class "Default")
      (node (ref "U4") (pin "25") (pinfunction "PA15_25") (pintype "bidirectional"))
    )
    (net (code "66") (name "unconnected-(U4-PB1-Pad15)") (class "Default")
      (node (ref "U4") (pin "15") (pinfunction "PB1_15") (pintype "bidirectional"))
    )
    (net (code "67") (name "unconnected-(U4-PB3-Pad26)") (class "Default")
      (node (ref "U4") (pin "26") (pinfunction "PB3_26") (pintype "bidirectional"))
    )
    (net (code "68") (name "unconnected-(U4-PB4-Pad27)") (class "Default")
      (node (ref "U4") (pin "27") (pinfunction "PB4_27") (pintype "bidirectional"))
    )
    (net (code "69") (name "unconnected-(U4-PB5-Pad28)") (class "Default")
      (node (ref "U4") (pin "28") (pinfunction "PB5_28") (pintype "bidirectional"))
    )
    (net (code "70") (name "unconnected-(U4-PB6-Pad29)") (class "Default")
      (node (ref "U4") (pin "29") (pinfunction "PB6_29") (pintype "bidirectional"))
    )
    (net (code "71") (name "unconnected-(U4-PB7-Pad30)") (class "Default")
      (node (ref "U4") (pin "30") (pinfunction "PB7_30") (pintype "bidirectional"))
    )
  )
)
